# design.net
KiCad netlist of a schematic drawn in Altium Designer
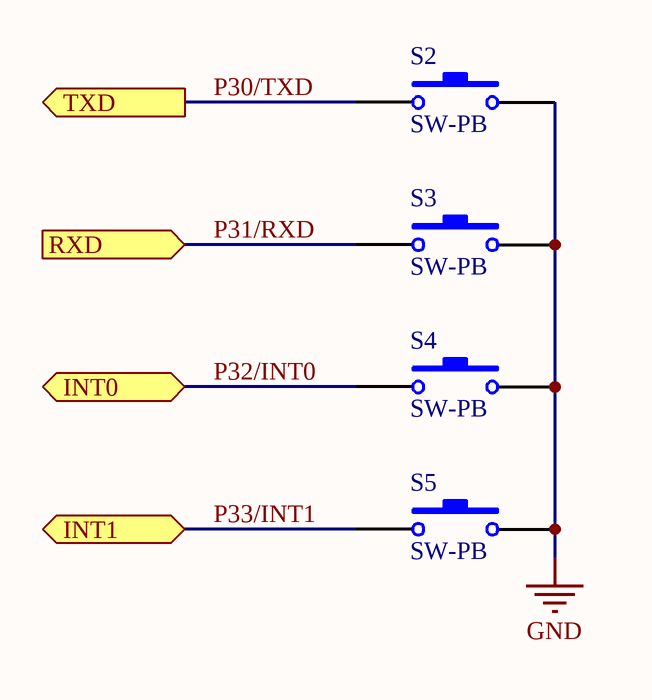
[diagram p0: 独立按键.SchDoc]

(export (version "E")
  (design (tool "Eeschema 10.0.6"))
  (components
    (comp (ref "S2")
      (value "SW-PB")
      (footprint "SPST-2")
      (description "Switch")
      (fields (field (name "PUBLISHER") "Altium Limited"))
      (libsource (lib "Miscellaneous Devices") (part "SW-PB"))
    )
    (comp (ref "S3")
      (value "SW-PB")
      (footprint "SPST-2")
      (description "Switch")
      (fields (field (name "PUBLISHER") "Altium Limited"))
      (libsource (lib "Miscellaneous Devices") (part "SW-PB"))
    )
    (comp (ref "S4")
      (value "SW-PB")
      (footprint "SPST-2")
      (description "Switch")
      (fields (field (name "PUBLISHER") "Altium Limited"))
      (libsource (lib "Miscellaneous Devices") (part "SW-PB"))
    )
    (comp (ref "S5")
      (value "SW-PB")
      (footprint "SPST-2")
      (description "Switch")
      (fields (field (name "PUBLISHER") "Altium Limited"))
      (libsource (lib "Miscellaneous Devices") (part "SW-PB"))
    )
  )
  (nets
    (net (code "1") (name "/P30{slash}TXD") (class "Default")
      (node (ref "S2") (pin "1") (pinfunction "1_1") (pintype "passive"))
    )
    (net (code "2") (name "/P31{slash}RXD") (class "Default")
      (node (ref "S3") (pin "1") (pinfunction "1_1") (pintype "passive"))
    )
    (net (code "3") (name "/P32{slash}INT0") (class "Default")
      (node (ref "S4") (pin "1") (pinfunction "1_1") (pintype "passive"))
    )
    (net (code "4") (name "/P33{slash}INT1") (class "Default")
      (node (ref "S5") (pin "1") (pinfunction "1_1") (pintype "passive"))
    )
    (net (code "5") (name "GND") (class "Default")
      (node (ref "S2") (pin "2") (pinfunction "2_2") (pintype "passive"))
      (node (ref "S3") (pin "2") (pinfunction "2_2") (pintype "passive"))
      (node (ref "S4") (pin "2") (pinfunction "2_2") (pintype "passive"))
      (node (ref "S5") (pin "2") (pinfunction "2_2") (pintype "passive"))
    )
  )
)
